# MainBoardR5.net
KiCad netlist of a schematic drawn in EAGLE
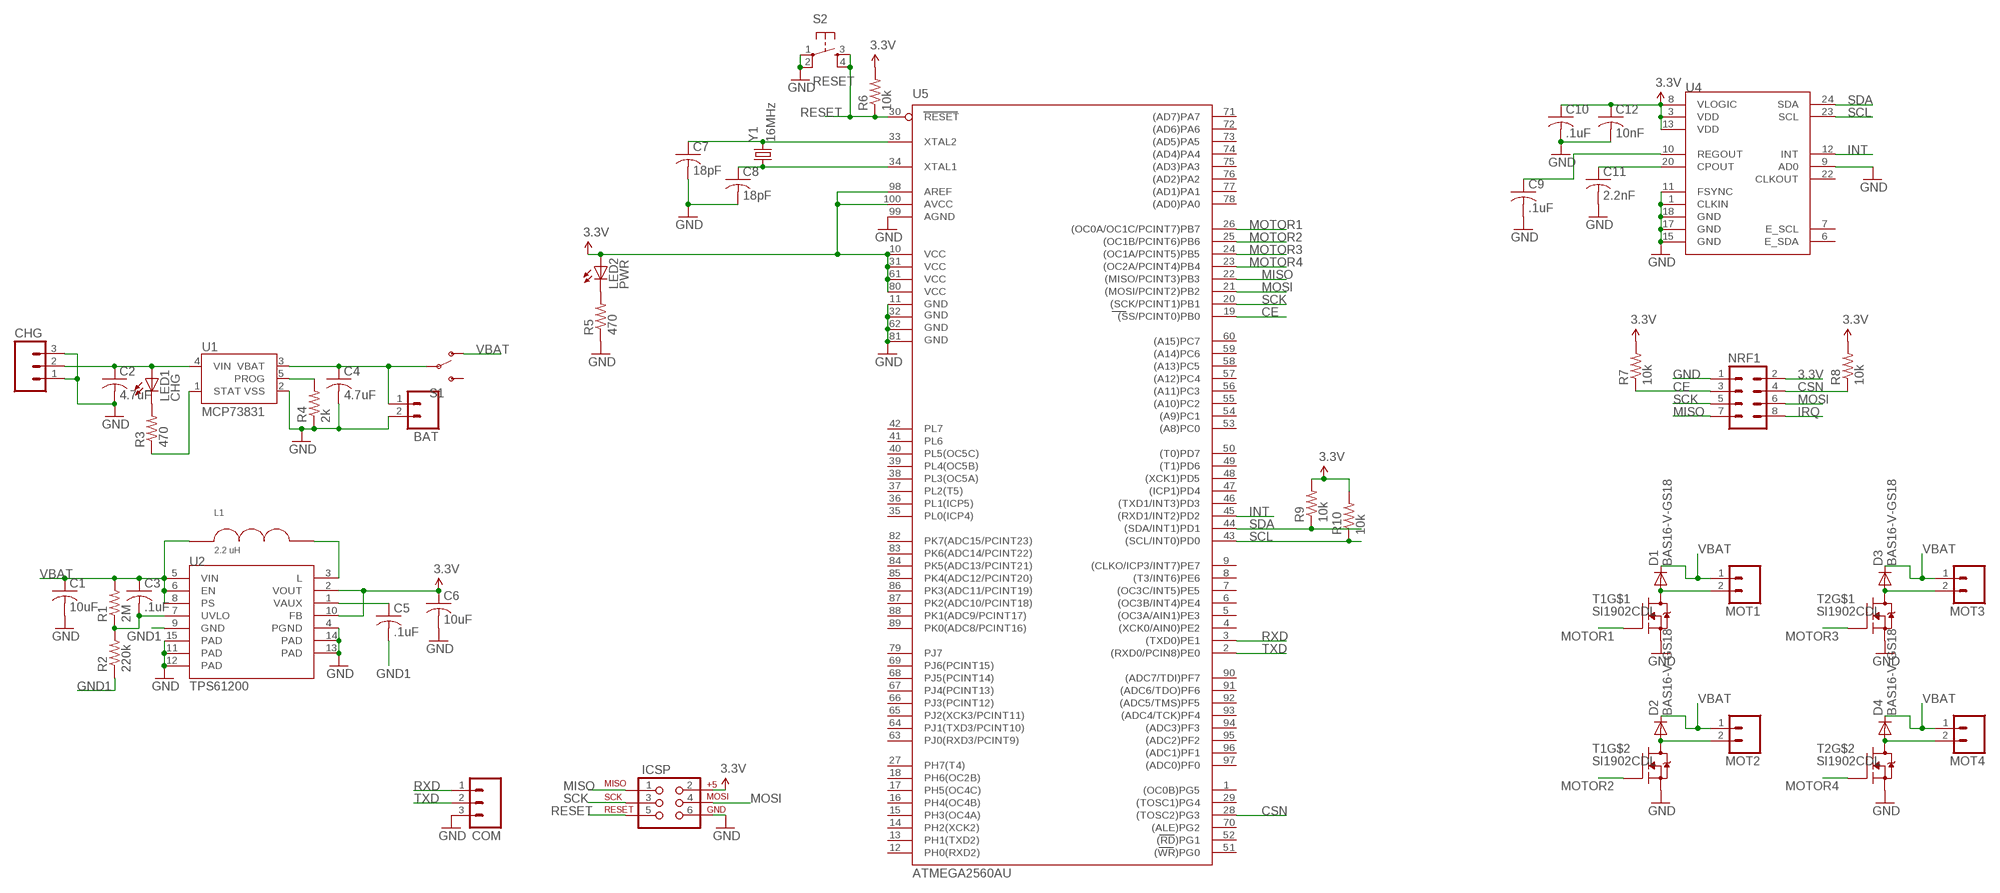
[diagram p0: schematic, sheet 1]

(export (version "E")
  (design (tool "Eeschema 10.0.6"))
  (components
    (comp (ref "BAT")
      (value "M02LOCK_LONGPADS")
      (footprint "eagle-import:1X02_LOCK_LONGPADS")
      (libsource (lib "eagle-import") (part "M02LOCK_LONGPADS"))
    )
    (comp (ref "C1")
      (value "10uF")
      (footprint "eagle-import:C0805")
      (libsource (lib "eagle-import") (part "C-USC0805"))
    )
    (comp (ref "C2")
      (value "4.7uF")
      (footprint "eagle-import:C0805")
      (libsource (lib "eagle-import") (part "C-USC0805"))
    )
    (comp (ref "C3")
      (value ".1uF")
      (footprint "eagle-import:C0805")
      (libsource (lib "eagle-import") (part "C-USC0805"))
    )
    (comp (ref "C4")
      (value "4.7uF")
      (footprint "eagle-import:C0805")
      (libsource (lib "eagle-import") (part "C-USC0805"))
    )
    (comp (ref "C5")
      (value ".1uF")
      (footprint "eagle-import:C0805")
      (libsource (lib "eagle-import") (part "C-USC0805"))
    )
    (comp (ref "C6")
      (value "10uF")
      (footprint "eagle-import:C0805")
      (libsource (lib "eagle-import") (part "C-USC0805"))
    )
    (comp (ref "C7")
      (value "18pF")
      (footprint "eagle-import:C0805")
      (libsource (lib "eagle-import") (part "C-USC0805"))
    )
    (comp (ref "C8")
      (value "18pF")
      (footprint "eagle-import:C0805")
      (libsource (lib "eagle-import") (part "C-USC0805"))
    )
    (comp (ref "C9")
      (value ".1uF")
      (footprint "eagle-import:C0805")
      (libsource (lib "eagle-import") (part "C-USC0805"))
    )
    (comp (ref "C10")
      (value ".1uF")
      (footprint "eagle-import:C0805")
      (libsource (lib "eagle-import") (part "C-USC0805"))
    )
    (comp (ref "C11")
      (value "2.2nF")
      (footprint "eagle-import:C0805")
      (libsource (lib "eagle-import") (part "C-USC0805"))
    )
    (comp (ref "C12")
      (value "10nF")
      (footprint "eagle-import:C0805")
      (libsource (lib "eagle-import") (part "C-USC0805"))
    )
    (comp (ref "CHG")
      (value "M03LONGPADS")
      (footprint "eagle-import:1X03_LONGPADS")
      (libsource (lib "eagle-import") (part "M03LONGPADS"))
    )
    (comp (ref "COM")
      (value "M03LONGPADS")
      (footprint "eagle-import:1X03_LONGPADS")
      (libsource (lib "eagle-import") (part "M03LONGPADS"))
    )
    (comp (ref "D1")
      (value "BAS16-V-GS18")
      (footprint "eagle-import:SOT23")
      (libsource (lib "eagle-import") (part "BAS16-V-GS18"))
    )
    (comp (ref "D2")
      (value "BAS16-V-GS18")
      (footprint "eagle-import:SOT23")
      (libsource (lib "eagle-import") (part "BAS16-V-GS18"))
    )
    (comp (ref "D3")
      (value "BAS16-V-GS18")
      (footprint "eagle-import:SOT23")
      (libsource (lib "eagle-import") (part "BAS16-V-GS18"))
    )
    (comp (ref "D4")
      (value "BAS16-V-GS18")
      (footprint "eagle-import:SOT23")
      (libsource (lib "eagle-import") (part "BAS16-V-GS18"))
    )
    (comp (ref "ICSP")
      (value "AVR_SPI_PRG_62X3_LOCK")
      (footprint "eagle-import:2X3_LOCK")
      (libsource (lib "eagle-import") (part "AVR_SPI_PRG_62X3_LOCK"))
    )
    (comp (ref "L1")
      (value "2.2 uH")
      (footprint "eagle-import:2518")
      (libsource (lib "eagle-import") (part "BRHL2518T2R2M"))
    )
    (comp (ref "LED1")
      (value "CHG")
      (footprint "eagle-import:LED-1206")
      (libsource (lib "eagle-import") (part "LED1206"))
    )
    (comp (ref "LED2")
      (value "PWR")
      (footprint "eagle-import:LED-1206")
      (libsource (lib "eagle-import") (part "LED1206"))
    )
    (comp (ref "MOT1")
      (value "M02LOCK_LONGPADS")
      (footprint "eagle-import:1X02_LOCK_LONGPADS")
      (libsource (lib "eagle-import") (part "M02LOCK_LONGPADS"))
    )
    (comp (ref "MOT2")
      (value "M02LOCK_LONGPADS")
      (footprint "eagle-import:1X02_LOCK_LONGPADS")
      (libsource (lib "eagle-import") (part "M02LOCK_LONGPADS"))
    )
    (comp (ref "MOT3")
      (value "M02LOCK_LONGPADS")
      (footprint "eagle-import:1X02_LOCK_LONGPADS")
      (libsource (lib "eagle-import") (part "M02LOCK_LONGPADS"))
    )
    (comp (ref "MOT4")
      (value "M02LOCK_LONGPADS")
      (footprint "eagle-import:1X02_LOCK_LONGPADS")
      (libsource (lib "eagle-import") (part "M02LOCK_LONGPADS"))
    )
    (comp (ref "NRF1")
      (value "M04X2")
      (footprint "eagle-import:2X4")
      (libsource (lib "eagle-import") (part "M04X2"))
    )
    (comp (ref "R1")
      (value "2M")
      (footprint "eagle-import:0805")
      (libsource (lib "eagle-import") (part "RESISTOR0805-RES"))
    )
    (comp (ref "R2")
      (value "220k")
      (footprint "eagle-import:0805")
      (libsource (lib "eagle-import") (part "RESISTOR0805-RES"))
    )
    (comp (ref "R3")
      (value "470")
      (footprint "eagle-import:0805")
      (libsource (lib "eagle-import") (part "RESISTOR0805-RES"))
    )
    (comp (ref "R4")
      (value "2k")
      (footprint "eagle-import:0805")
      (libsource (lib "eagle-import") (part "RESISTOR0805-RES"))
    )
    (comp (ref "R5")
      (value "470")
      (footprint "eagle-import:0805")
      (libsource (lib "eagle-import") (part "RESISTOR0805-RES"))
    )
    (comp (ref "R6")
      (value "10k")
      (footprint "eagle-import:0805")
      (libsource (lib "eagle-import") (part "RESISTOR0805-RES"))
    )
    (comp (ref "R7")
      (value "10k")
      (footprint "eagle-import:0805")
      (libsource (lib "eagle-import") (part "RESISTOR0805-RES"))
    )
    (comp (ref "R8")
      (value "10k")
      (footprint "eagle-import:0805")
      (libsource (lib "eagle-import") (part "RESISTOR0805-RES"))
    )
    (comp (ref "R9")
      (value "10k")
      (footprint "eagle-import:0805")
      (libsource (lib "eagle-import") (part "RESISTOR0805-RES"))
    )
    (comp (ref "R10")
      (value "10k")
      (footprint "eagle-import:0805")
      (libsource (lib "eagle-import") (part "RESISTOR0805-RES"))
    )
    (comp (ref "S1")
      (value "SWITCH-SPST-SMD-A")
      (footprint "eagle-import:SWITCH-SPST-SMD-A")
      (libsource (lib "eagle-import") (part "SWITCH-SPST-SMD-A"))
    )
    (comp (ref "S2")
      (value "RESET")
      (footprint "eagle-import:TACTILE_SWITCH_SMD")
      (libsource (lib "eagle-import") (part "TAC_SWITCHSMD"))
    )
    (comp (ref "T1")
      (value "SI1902CDL")
      (footprint "eagle-import:SOT363_INFINEON")
      (libsource (lib "eagle-import") (part "SI1902CDL"))
    )
    (comp (ref "T2")
      (value "SI1902CDL")
      (footprint "eagle-import:SOT363_INFINEON")
      (libsource (lib "eagle-import") (part "SI1902CDL"))
    )
    (comp (ref "U1")
      (value "MCP73831")
      (footprint "eagle-import:SOT23-5")
      (libsource (lib "eagle-import") (part "MCP73831"))
    )
    (comp (ref "U2")
      (value "TPS61200")
      (footprint "eagle-import:QFN-10_PAD")
      (libsource (lib "eagle-import") (part "TPS61200"))
    )
    (comp (ref "U4")
      (value "MPU-9150QFN-24-NP")
      (footprint "eagle-import:QFN-24-NP")
      (libsource (lib "eagle-import") (part "MPU-9150QFN-24-NP"))
    )
    (comp (ref "U5")
      (value "ATMEGA2560AU")
      (footprint "eagle-import:TQFP100")
      (libsource (lib "eagle-import") (part "ATMEGA2560AU"))
    )
    (comp (ref "Y1")
      (value "16MHz")
      (footprint "eagle-import:CRYSTAL-SMD-5X3")
      (libsource (lib "eagle-import") (part "CRYSTAL5X3"))
    )
  )
  (nets
    (net (code "1") (name "/CE") (class "Default")
      (node (ref "NRF1") (pin "3") (pinfunction "3_3") (pintype "passive"))
      (node (ref "R7") (pin "1") (pinfunction "1_1") (pintype "passive"))
      (node (ref "U5") (pin "19") (pinfunction "(SS/PCINT0)PB0_19") (pintype "bidirectional"))
    )
    (net (code "2") (name "/CSN") (class "Default")
      (node (ref "NRF1") (pin "4") (pinfunction "4_4") (pintype "passive"))
      (node (ref "R8") (pin "1") (pinfunction "1_1") (pintype "passive"))
      (node (ref "U5") (pin "28") (pinfunction "(TOSC2)PG3_28") (pintype "bidirectional"))
    )
    (net (code "3") (name "/GND1") (class "Default")
      (node (ref "C5") (pin "2") (pinfunction "2_2") (pintype "passive"))
      (node (ref "R2") (pin "1") (pinfunction "1_1") (pintype "passive"))
      (node (ref "U2") (pin "9") (pinfunction "GND_9") (pintype "power_in"))
    )
    (net (code "4") (name "/INT") (class "Default")
      (node (ref "U4") (pin "12") (pinfunction "INT_12") (pintype "bidirectional"))
      (node (ref "U5") (pin "45") (pinfunction "(RXD1/INT2)PD2_45") (pintype "bidirectional"))
    )
    (net (code "5") (name "/IRQ") (class "Default")
      (node (ref "NRF1") (pin "8") (pinfunction "8_8") (pintype "passive"))
    )
    (net (code "6") (name "/MISO") (class "Default")
      (node (ref "ICSP") (pin "1") (pinfunction "1_1") (pintype "passive"))
      (node (ref "NRF1") (pin "7") (pinfunction "7_7") (pintype "passive"))
      (node (ref "U5") (pin "22") (pinfunction "(MISO/PCINT3)PB3_22") (pintype "bidirectional"))
    )
    (net (code "7") (name "/MOSI") (class "Default")
      (node (ref "ICSP") (pin "4") (pinfunction "4_4") (pintype "passive"))
      (node (ref "NRF1") (pin "6") (pinfunction "6_6") (pintype "passive"))
      (node (ref "U5") (pin "21") (pinfunction "(MOSI/PCINT2)PB2_21") (pintype "bidirectional"))
    )
    (net (code "8") (name "/MOTOR1") (class "Default")
      (node (ref "T1") (pin "2") (pinfunction "G_2") (pintype "passive"))
      (node (ref "U5") (pin "26") (pinfunction "(OC0A/OC1C/PCINT7)PB7_26") (pintype "bidirectional"))
    )
    (net (code "9") (name "/MOTOR2") (class "Default")
      (node (ref "T1") (pin "5") (pinfunction "G_5") (pintype "passive"))
      (node (ref "U5") (pin "25") (pinfunction "(OC1B/PCINT6)PB6_25") (pintype "bidirectional"))
    )
    (net (code "10") (name "/MOTOR3") (class "Default")
      (node (ref "T2") (pin "2") (pinfunction "G_2") (pintype "passive"))
      (node (ref "U5") (pin "24") (pinfunction "(OC1A/PCINT5)PB5_24") (pintype "bidirectional"))
    )
    (net (code "11") (name "/MOTOR4") (class "Default")
      (node (ref "T2") (pin "5") (pinfunction "G_5") (pintype "passive"))
      (node (ref "U5") (pin "23") (pinfunction "(OC2A/PCINT4)PB4_23") (pintype "bidirectional"))
    )
    (net (code "12") (name "/RESET") (class "Default")
      (node (ref "ICSP") (pin "5") (pinfunction "5_5") (pintype "passive"))
      (node (ref "R6") (pin "1") (pinfunction "1_1") (pintype "passive"))
      (node (ref "S2") (pin "3") (pinfunction "3_3") (pintype "passive"))
      (node (ref "S2") (pin "4") (pinfunction "4_4") (pintype "passive"))
      (node (ref "U5") (pin "30") (pinfunction "RESET_30") (pintype "input"))
    )
    (net (code "13") (name "/RXD") (class "Default")
      (node (ref "COM") (pin "1") (pinfunction "1_1") (pintype "passive"))
      (node (ref "U5") (pin "3") (pinfunction "(TXD0)PE1_3") (pintype "bidirectional"))
    )
    (net (code "14") (name "/SCK") (class "Default")
      (node (ref "ICSP") (pin "3") (pinfunction "3_3") (pintype "passive"))
      (node (ref "NRF1") (pin "5") (pinfunction "5_5") (pintype "passive"))
      (node (ref "U5") (pin "20") (pinfunction "(SCK/PCINT1)PB1_20") (pintype "bidirectional"))
    )
    (net (code "15") (name "/SCL") (class "Default")
      (node (ref "R10") (pin "1") (pinfunction "1_1") (pintype "passive"))
      (node (ref "U4") (pin "23") (pinfunction "SCL_23") (pintype "bidirectional"))
      (node (ref "U5") (pin "43") (pinfunction "(SCL/INT0)PD0_43") (pintype "bidirectional"))
    )
    (net (code "16") (name "/SDA") (class "Default")
      (node (ref "R9") (pin "1") (pinfunction "1_1") (pintype "passive"))
      (node (ref "U4") (pin "24") (pinfunction "SDA_24") (pintype "bidirectional"))
      (node (ref "U5") (pin "44") (pinfunction "(SDA/INT1)PD1_44") (pintype "bidirectional"))
    )
    (net (code "17") (name "/TXD") (class "Default")
      (node (ref "COM") (pin "2") (pinfunction "2_2") (pintype "passive"))
      (node (ref "U5") (pin "2") (pinfunction "(RXD0/PCIN8)PE0_2") (pintype "bidirectional"))
    )
    (net (code "18") (name "/VBAT") (class "Default")
      (node (ref "C1") (pin "1") (pinfunction "1_1") (pintype "passive"))
      (node (ref "C3") (pin "1") (pinfunction "1_1") (pintype "passive"))
      (node (ref "D1") (pin "3") (pinfunction "C_3") (pintype "passive"))
      (node (ref "D2") (pin "3") (pinfunction "C_3") (pintype "passive"))
      (node (ref "D3") (pin "3") (pinfunction "C_3") (pintype "passive"))
      (node (ref "D4") (pin "3") (pinfunction "C_3") (pintype "passive"))
      (node (ref "L1") (pin "P$1") (pinfunction "1_P$1") (pintype "bidirectional"))
      (node (ref "MOT1") (pin "1") (pinfunction "1_1") (pintype "passive"))
      (node (ref "MOT2") (pin "1") (pinfunction "1_1") (pintype "passive"))
      (node (ref "MOT3") (pin "1") (pinfunction "1_1") (pintype "passive"))
      (node (ref "MOT4") (pin "1") (pinfunction "1_1") (pintype "passive"))
      (node (ref "R1") (pin "2") (pinfunction "2_2") (pintype "passive"))
      (node (ref "S1") (pin "1") (pinfunction "O_1") (pintype "passive"))
      (node (ref "U2") (pin "5") (pinfunction "VIN_5") (pintype "power_in"))
      (node (ref "U2") (pin "6") (pinfunction "EN_6") (pintype "input"))
      (node (ref "U2") (pin "8") (pinfunction "PS_8") (pintype "input"))
    )
    (net (code "19") (name "3.3V") (class "Default")
      (node (ref "C10") (pin "1") (pinfunction "1_1") (pintype "passive"))
      (node (ref "C12") (pin "1") (pinfunction "1_1") (pintype "passive"))
      (node (ref "C6") (pin "1") (pinfunction "1_1") (pintype "passive"))
      (node (ref "ICSP") (pin "2") (pinfunction "2_2") (pintype "passive"))
      (node (ref "LED2") (pin "A") (pinfunction "A_A") (pintype "passive"))
      (node (ref "NRF1") (pin "2") (pinfunction "2_2") (pintype "passive"))
      (node (ref "R10") (pin "2") (pinfunction "2_2") (pintype "passive"))
      (node (ref "R6") (pin "2") (pinfunction "2_2") (pintype "passive"))
      (node (ref "R7") (pin "2") (pinfunction "2_2") (pintype "passive"))
      (node (ref "R8") (pin "2") (pinfunction "2_2") (pintype "passive"))
      (node (ref "R9") (pin "2") (pinfunction "2_2") (pintype "passive"))
      (node (ref "U2") (pin "10") (pinfunction "FB_10") (pintype "passive"))
      (node (ref "U2") (pin "2") (pinfunction "VOUT_2") (pintype "passive"))
      (node (ref "U4") (pin "13") (pinfunction "VDD_13") (pintype "bidirectional"))
      (node (ref "U4") (pin "3") (pinfunction "VDD_3") (pintype "bidirectional"))
      (node (ref "U4") (pin "8") (pinfunction "VLOGIC_8") (pintype "bidirectional"))
      (node (ref "U5") (pin "10") (pinfunction "VCC_10") (pintype "power_in"))
      (node (ref "U5") (pin "100") (pinfunction "AVCC_100") (pintype "power_in"))
      (node (ref "U5") (pin "31") (pinfunction "VCC1_31") (pintype "power_in"))
      (node (ref "U5") (pin "61") (pinfunction "VCC2_61") (pintype "power_in"))
      (node (ref "U5") (pin "80") (pinfunction "VCC3_80") (pintype "power_in"))
      (node (ref "U5") (pin "98") (pinfunction "AREF_98") (pintype "bidirectional"))
    )
    (net (code "20") (name "GND") (class "Default")
      (node (ref "BAT") (pin "2") (pinfunction "2_2") (pintype "passive"))
      (node (ref "C1") (pin "2") (pinfunction "2_2") (pintype "passive"))
      (node (ref "C10") (pin "2") (pinfunction "2_2") (pintype "passive"))
      (node (ref "C11") (pin "2") (pinfunction "2_2") (pintype "passive"))
      (node (ref "C12") (pin "2") (pinfunction "2_2") (pintype "passive"))
      (node (ref "C2") (pin "2") (pinfunction "2_2") (pintype "passive"))
      (node (ref "C4") (pin "2") (pinfunction "2_2") (pintype "passive"))
      (node (ref "C6") (pin "2") (pinfunction "2_2") (pintype "passive"))
      (node (ref "C7") (pin "2") (pinfunction "2_2") (pintype "passive"))
      (node (ref "C8") (pin "2") (pinfunction "2_2") (pintype "passive"))
      (node (ref "C9") (pin "2") (pinfunction "2_2") (pintype "passive"))
      (node (ref "CHG") (pin "1") (pinfunction "1_1") (pintype "passive"))
      (node (ref "CHG") (pin "3") (pinfunction "3_3") (pintype "passive"))
      (node (ref "COM") (pin "3") (pinfunction "3_3") (pintype "passive"))
      (node (ref "ICSP") (pin "6") (pinfunction "6_6") (pintype "passive"))
      (node (ref "NRF1") (pin "1") (pinfunction "1_1") (pintype "passive"))
      (node (ref "R4") (pin "1") (pinfunction "1_1") (pintype "passive"))
      (node (ref "R5") (pin "1") (pinfunction "1_1") (pintype "passive"))
      (node (ref "S2") (pin "1") (pinfunction "1_1") (pintype "passive"))
      (node (ref "S2") (pin "2") (pinfunction "2_2") (pintype "passive"))
      (node (ref "T1") (pin "1") (pinfunction "S_1") (pintype "passive"))
      (node (ref "T1") (pin "4") (pinfunction "S_4") (pintype "passive"))
      (node (ref "T2") (pin "1") (pinfunction "S_1") (pintype "passive"))
      (node (ref "T2") (pin "4") (pinfunction "S_4") (pintype "passive"))
      (node (ref "U1") (pin "2") (pinfunction "VSS_2") (pintype "power_in"))
      (node (ref "U2") (pin "11") (pinfunction "PAD_11") (pintype "power_in"))
      (node (ref "U2") (pin "12") (pinfunction "PAD_12") (pintype "power_in"))
      (node (ref "U2") (pin "13") (pinfunction "PAD_13") (pintype "power_in"))
      (node (ref "U2") (pin "14") (pinfunction "PAD_14") (pintype "power_in"))
      (node (ref "U2") (pin "15") (pinfunction "PAD_15") (pintype "power_in"))
      (node (ref "U2") (pin "4") (pinfunction "PGND_4") (pintype "power_in"))
      (node (ref "U4") (pin "1") (pinfunction "CLKIN_1") (pintype "bidirectional"))
      (node (ref "U4") (pin "11") (pinfunction "FSYNC_11") (pintype "bidirectional"))
      (node (ref "U4") (pin "15") (pinfunction "GND_15") (pintype "bidirectional"))
      (node (ref "U4") (pin "17") (pinfunction "GND_17") (pintype "bidirectional"))
      (node (ref "U4") (pin "18") (pinfunction "GND_18") (pintype "bidirectional"))
      (node (ref "U4") (pin "9") (pinfunction "AD0_9") (pintype "bidirectional"))
      (node (ref "U5") (pin "11") (pinfunction "GND_11") (pintype "power_in"))
      (node (ref "U5") (pin "32") (pinfunction "GND1_32") (pintype "power_in"))
      (node (ref "U5") (pin "62") (pinfunction "GND2_62") (pintype "power_in"))
      (node (ref "U5") (pin "81") (pinfunction "GND3_81") (pintype "power_in"))
      (node (ref "U5") (pin "99") (pinfunction "AGND_99") (pintype "power_in"))
    )
    (net (code "21") (name "Net-(D1-A)") (class "Default")
      (node (ref "D1") (pin "1") (pinfunction "A_1") (pintype "passive"))
      (node (ref "MOT1") (pin "2") (pinfunction "2_2") (pintype "passive"))
      (node (ref "T1") (pin "6") (pinfunction "D_6") (pintype "passive"))
    )
    (net (code "22") (name "Net-(D2-A)") (class "Default")
      (node (ref "D2") (pin "1") (pinfunction "A_1") (pintype "passive"))
      (node (ref "MOT2") (pin "2") (pinfunction "2_2") (pintype "passive"))
      (node (ref "T1") (pin "3") (pinfunction "D_3") (pintype "passive"))
    )
    (net (code "23") (name "Net-(D3-A)") (class "Default")
      (node (ref "D3") (pin "1") (pinfunction "A_1") (pintype "passive"))
      (node (ref "MOT3") (pin "2") (pinfunction "2_2") (pintype "passive"))
      (node (ref "T2") (pin "6") (pinfunction "D_6") (pintype "passive"))
    )
    (net (code "24") (name "Net-(D4-A)") (class "Default")
      (node (ref "D4") (pin "1") (pinfunction "A_1") (pintype "passive"))
      (node (ref "MOT4") (pin "2") (pinfunction "2_2") (pintype "passive"))
      (node (ref "T2") (pin "3") (pinfunction "D_3") (pintype "passive"))
    )
    (net (code "25") (name "Net-(L1-2)") (class "Default")
      (node (ref "L1") (pin "P$2") (pinfunction "2_P$2") (pintype "bidirectional"))
      (node (ref "U2") (pin "3") (pinfunction "L_3") (pintype "passive"))
    )
    (net (code "26") (name "Net-(LED1-PadC)") (class "Default")
      (node (ref "LED1") (pin "C") (pinfunction "C_C") (pintype "passive"))
      (node (ref "R3") (pin "2") (pinfunction "2_2") (pintype "passive"))
    )
    (net (code "27") (name "Net-(LED2-PadC)") (class "Default")
      (node (ref "LED2") (pin "C") (pinfunction "C_C") (pintype "passive"))
      (node (ref "R5") (pin "2") (pinfunction "2_2") (pintype "passive"))
    )
    (net (code "28") (name "Net-(S1-P)") (class "Default")
      (node (ref "BAT") (pin "1") (pinfunction "1_1") (pintype "passive"))
      (node (ref "C4") (pin "1") (pinfunction "1_1") (pintype "passive"))
      (node (ref "S1") (pin "2") (pinfunction "P_2") (pintype "passive"))
      (node (ref "U1") (pin "3") (pinfunction "VBAT_3") (pintype "power_in"))
    )
    (net (code "29") (name "Net-(U1-PROG)") (class "Default")
      (node (ref "R4") (pin "2") (pinfunction "2_2") (pintype "passive"))
      (node (ref "U1") (pin "5") (pinfunction "PROG_5") (pintype "input"))
    )
    (net (code "30") (name "Net-(U1-STAT)") (class "Default")
      (node (ref "R3") (pin "1") (pinfunction "1_1") (pintype "passive"))
      (node (ref "U1") (pin "1") (pinfunction "STAT_1") (pintype "output"))
    )
    (net (code "31") (name "Net-(U1-VIN)") (class "Default")
      (node (ref "C2") (pin "1") (pinfunction "1_1") (pintype "passive"))
      (node (ref "CHG") (pin "2") (pinfunction "2_2") (pintype "passive"))
      (node (ref "LED1") (pin "A") (pinfunction "A_A") (pintype "passive"))
      (node (ref "U1") (pin "4") (pinfunction "VIN_4") (pintype "power_in"))
    )
    (net (code "32") (name "Net-(U2-UVLO)") (class "Default")
      (node (ref "C3") (pin "2") (pinfunction "2_2") (pintype "passive"))
      (node (ref "R1") (pin "1") (pinfunction "1_1") (pintype "passive"))
      (node (ref "R2") (pin "2") (pinfunction "2_2") (pintype "passive"))
      (node (ref "U2") (pin "7") (pinfunction "UVLO_7") (pintype "passive"))
    )
    (net (code "33") (name "Net-(U2-VAUX)") (class "Default")
      (node (ref "C5") (pin "1") (pinfunction "1_1") (pintype "passive"))
      (node (ref "U2") (pin "1") (pinfunction "VAUX_1") (pintype "passive"))
    )
    (net (code "34") (name "Net-(U4-CPOUT)") (class "Default")
      (node (ref "C11") (pin "1") (pinfunction "1_1") (pintype "passive"))
      (node (ref "U4") (pin "20") (pinfunction "CPOUT_20") (pintype "bidirectional"))
    )
    (net (code "35") (name "Net-(U4-REGOUT)") (class "Default")
      (node (ref "C9") (pin "1") (pinfunction "1_1") (pintype "passive"))
      (node (ref "U4") (pin "10") (pinfunction "REGOUT_10") (pintype "bidirectional"))
    )
    (net (code "36") (name "Net-(U5-XTAL1)") (class "Default")
      (node (ref "C8") (pin "1") (pinfunction "1_1") (pintype "passive"))
      (node (ref "U5") (pin "34") (pinfunction "XTAL1_34") (pintype "input"))
      (node (ref "Y1") (pin "1") (pinfunction "1_1") (pintype "passive"))
    )
    (net (code "37") (name "Net-(U5-XTAL2)") (class "Default")
      (node (ref "C7") (pin "1") (pinfunction "1_1") (pintype "passive"))
      (node (ref "U5") (pin "33") (pinfunction "XTAL2_33") (pintype "output"))
      (node (ref "Y1") (pin "3") (pinfunction "2_3") (pintype "passive"))
    )
    (net (code "38") (name "unconnected-(S1-S-Pad3)") (class "Default")
      (node (ref "S1") (pin "3") (pinfunction "S_3") (pintype "passive"))
    )
    (net (code "39") (name "unconnected-(U4-CLKOUT-Pad22)") (class "Default")
      (node (ref "U4") (pin "22") (pinfunction "CLKOUT_22") (pintype "bidirectional"))
    )
    (net (code "40") (name "unconnected-(U4-E_SCL-Pad7)") (class "Default")
      (node (ref "U4") (pin "7") (pinfunction "E_SCL_7") (pintype "bidirectional"))
    )
    (net (code "41") (name "unconnected-(U4-E_SDA-Pad6)") (class "Default")
      (node (ref "U4") (pin "6") (pinfunction "E_SDA_6") (pintype "bidirectional"))
    )
    (net (code "42") (name "unconnected-(U5-(A8)PC0-Pad53)") (class "Default")
      (node (ref "U5") (pin "53") (pinfunction "(A8)PC0_53") (pintype "bidirectional"))
    )
    (net (code "43") (name "unconnected-(U5-(A9)PC1-Pad54)") (class "Default")
      (node (ref "U5") (pin "54") (pinfunction "(A9)PC1_54") (pintype "bidirectional"))
    )
    (net (code "44") (name "unconnected-(U5-(A10)PC2-Pad55)") (class "Default")
      (node (ref "U5") (pin "55") (pinfunction "(A10)PC2_55") (pintype "bidirectional"))
    )
    (net (code "45") (name "unconnected-(U5-(A11)PC3-Pad56)") (class "Default")
      (node (ref "U5") (pin "56") (pinfunction "(A11)PC3_56") (pintype "bidirectional"))
    )
    (net (code "46") (name "unconnected-(U5-(A12)PC4-Pad57)") (class "Default")
      (node (ref "U5") (pin "57") (pinfunction "(A12)PC4_57") (pintype "bidirectional"))
    )
    (net (code "47") (name "unconnected-(U5-(A13)PC5-Pad58)") (class "Default")
      (node (ref "U5") (pin "58") (pinfunction "(A13)PC5_58") (pintype "bidirectional"))
    )
    (net (code "48") (name "unconnected-(U5-(A14)PC6-Pad59)") (class "Default")
      (node (ref "U5") (pin "59") (pinfunction "(A14)PC6_59") (pintype "bidirectional"))
    )
    (net (code "49") (name "unconnected-(U5-(A15)PC7-Pad60)") (class "Default")
      (node (ref "U5") (pin "60") (pinfunction "(A15)PC7_60") (pintype "bidirectional"))
    )
    (net (code "50") (name "unconnected-(U5-(AD0)PA0-Pad78)") (class "Default")
      (node (ref "U5") (pin "78") (pinfunction "(AD0)PA0_78") (pintype "bidirectional"))
    )
    (net (code "51") (name "unconnected-(U5-(AD1)PA1-Pad77)") (class "Default")
      (node (ref "U5") (pin "77") (pinfunction "(AD1)PA1_77") (pintype "bidirectional"))
    )
    (net (code "52") (name "unconnected-(U5-(AD2)PA2-Pad76)") (class "Default")
      (node (ref "U5") (pin "76") (pinfunction "(AD2)PA2_76") (pintype "bidirectional"))
    )
    (net (code "53") (name "unconnected-(U5-(AD3)PA3-Pad75)") (class "Default")
      (node (ref "U5") (pin "75") (pinfunction "(AD3)PA3_75") (pintype "bidirectional"))
    )
    (net (code "54") (name "unconnected-(U5-(AD4)PA4-Pad74)") (class "Default")
      (node (ref "U5") (pin "74") (pinfunction "(AD4)PA4_74") (pintype "bidirectional"))
    )
    (net (code "55") (name "unconnected-(U5-(AD5)PA5-Pad73)") (class "Default")
      (node (ref "U5") (pin "73") (pinfunction "(AD5)PA5_73") (pintype "bidirectional"))
    )
    (net (code "56") (name "unconnected-(U5-(AD6)PA6-Pad72)") (class "Default")
      (node (ref "U5") (pin "72") (pinfunction "(AD6)PA6_72") (pintype "bidirectional"))
    )
    (net (code "57") (name "unconnected-(U5-(AD7)PA7-Pad71)") (class "Default")
      (node (ref "U5") (pin "71") (pinfunction "(AD7)PA7_71") (pintype "bidirectional"))
    )
    (net (code "58") (name "unconnected-(U5-(ADC0)PF0-Pad97)") (class "Default")
      (node (ref "U5") (pin "97") (pinfunction "(ADC0)PF0_97") (pintype "bidirectional"))
    )
    (net (code "59") (name "unconnected-(U5-(ADC1)PF1-Pad96)") (class "Default")
      (node (ref "U5") (pin "96") (pinfunction "(ADC1)PF1_96") (pintype "bidirectional"))
    )
    (net (code "60") (name "unconnected-(U5-(ADC2)PF2-Pad95)") (class "Default")
      (node (ref "U5") (pin "95") (pinfunction "(ADC2)PF2_95") (pintype "bidirectional"))
    )
    (net (code "61") (name "unconnected-(U5-(ADC3)PF3-Pad94)") (class "Default")
      (node (ref "U5") (pin "94") (pinfunction "(ADC3)PF3_94") (pintype "bidirectional"))
    )
    (net (code "62") (name "unconnected-(U5-(ADC4{slash}TCK)PF4-Pad93)") (class "Default")
      (node (ref "U5") (pin "93") (pinfunction "(ADC4/TCK)PF4_93") (pintype "bidirectional"))
    )
    (net (code "63") (name "unconnected-(U5-(ADC5{slash}TMS)PF5-Pad92)") (class "Default")
      (node (ref "U5") (pin "92") (pinfunction "(ADC5/TMS)PF5_92") (pintype "bidirectional"))
    )
    (net (code "64") (name "unconnected-(U5-(ADC6{slash}TDO)PF6-Pad91)") (class "Default")
      (node (ref "U5") (pin "91") (pinfunction "(ADC6/TDO)PF6_91") (pintype "bidirectional"))
    )
    (net (code "65") (name "unconnected-(U5-(ADC7{slash}TDI)PF7-Pad90)") (class "Default")
      (node (ref "U5") (pin "90") (pinfunction "(ADC7/TDI)PF7_90") (pintype "bidirectional"))
    )
    (net (code "66") (name "unconnected-(U5-(ALE)PG2-Pad70)") (class "Default")
      (node (ref "U5") (pin "70") (pinfunction "(ALE)PG2_70") (pintype "bidirectional"))
    )
    (net (code "67") (name "unconnected-(U5-(CLKO{slash}ICP3{slash}INT7)PE7-Pad9)") (class "Default")
      (node (ref "U5") (pin "9") (pinfunction "(CLKO/ICP3/INT7)PE7_9") (pintype "bidirectional"))
    )
    (net (code "68") (name "unconnected-(U5-(ICP1)PD4-Pad47)") (class "Default")
      (node (ref "U5") (pin "47") (pinfunction "(ICP1)PD4_47") (pintype "bidirectional"))
    )
    (net (code "69") (name "unconnected-(U5-(OC0B)PG5-Pad1)") (class "Default")
      (node (ref "U5") (pin "1") (pinfunction "(OC0B)PG5_1") (pintype "bidirectional"))
    )
    (net (code "70") (name "unconnected-(U5-(OC3A{slash}AIN1)PE3-Pad5)") (class "Default")
      (node (ref "U5") (pin "5") (pinfunction "(OC3A/AIN1)PE3_5") (pintype "bidirectional"))
    )
    (net (code "71") (name "unconnected-(U5-(OC3B{slash}INT4)PE4-Pad6)") (class "Default")
      (node (ref "U5") (pin "6") (pinfunction "(OC3B/INT4)PE4_6") (pintype "bidirectional"))
    )
    (net (code "72") (name "unconnected-(U5-(OC3C{slash}INT5)PE5-Pad7)") (class "Default")
      (node (ref "U5") (pin "7") (pinfunction "(OC3C/INT5)PE5_7") (pintype "bidirectional"))
    )
    (net (code "73") (name "unconnected-(U5-(RD)PG1-Pad52)") (class "Default")
      (node (ref "U5") (pin "52") (pinfunction "(RD)PG1_52") (pintype "bidirectional"))
    )
    (net (code "74") (name "unconnected-(U5-(T0)PD7-Pad50)") (class "Default")
      (node (ref "U5") (pin "50") (pinfunction "(T0)PD7_50") (pintype "bidirectional"))
    )
    (net (code "75") (name "unconnected-(U5-(T1)PD6-Pad49)") (class "Default")
      (node (ref "U5") (pin "49") (pinfunction "(T1)PD6_49") (pintype "bidirectional"))
    )
    (net (code "76") (name "unconnected-(U5-(T3{slash}INT6)PE6-Pad8)") (class "Default")
      (node (ref "U5") (pin "8") (pinfunction "(T3/INT6)PE6_8") (pintype "bidirectional"))
    )
    (net (code "77") (name "unconnected-(U5-(TOSC1)PG4-Pad29)") (class "Default")
      (node (ref "U5") (pin "29") (pinfunction "(TOSC1)PG4_29") (pintype "bidirectional"))
    )
    (net (code "78") (name "unconnected-(U5-(TXD1{slash}INT3)PD3-Pad46)") (class "Default")
      (node (ref "U5") (pin "46") (pinfunction "(TXD1/INT3)PD3_46") (pintype "bidirectional"))
    )
    (net (code "79") (name "unconnected-(U5-(WR)PG0-Pad51)") (class "Default")
      (node (ref "U5") (pin "51") (pinfunction "(WR)PG0_51") (pintype "bidirectional"))
    )
    (net (code "80") (name "unconnected-(U5-(XCK0{slash}AIN0)PE2-Pad4)") (class "Default")
      (node (ref "U5") (pin "4") (pinfunction "(XCK0/AIN0)PE2_4") (pintype "bidirectional"))
    )
    (net (code "81") (name "unconnected-(U5-(XCK1)PD5-Pad48)") (class "Default")
      (node (ref "U5") (pin "48") (pinfunction "(XCK1)PD5_48") (pintype "bidirectional"))
    )
    (net (code "82") (name "unconnected-(U5-PH0(RXD2)-Pad12)") (class "Default")
      (node (ref "U5") (pin "12") (pinfunction "PH0(RXD2)_12") (pintype "bidirectional"))
    )
    (net (code "83") (name "unconnected-(U5-PH1(TXD2)-Pad13)") (class "Default")
      (node (ref "U5") (pin "13") (pinfunction "PH1(TXD2)_13") (pintype "bidirectional"))
    )
    (net (code "84") (name "unconnected-(U5-PH2(XCK2)-Pad14)") (class "Default")
      (node (ref "U5") (pin "14") (pinfunction "PH2(XCK2)_14") (pintype "bidirectional"))
    )
    (net (code "85") (name "unconnected-(U5-PH3(OC4A)-Pad15)") (class "Default")
      (node (ref "U5") (pin "15") (pinfunction "PH3(OC4A)_15") (pintype "bidirectional"))
    )
    (net (code "86") (name "unconnected-(U5-PH4(OC4B)-Pad16)") (class "Default")
      (node (ref "U5") (pin "16") (pinfunction "PH4(OC4B)_16") (pintype "bidirectional"))
    )
    (net (code "87") (name "unconnected-(U5-PH5(OC4C)-Pad17)") (class "Default")
      (node (ref "U5") (pin "17") (pinfunction "PH5(OC4C)_17") (pintype "bidirectional"))
    )
    (net (code "88") (name "unconnected-(U5-PH6(OC2B)-Pad18)") (class "Default")
      (node (ref "U5") (pin "18") (pinfunction "PH6(OC2B)_18") (pintype "bidirectional"))
    )
    (net (code "89") (name "unconnected-(U5-PH7(T4)-Pad27)") (class "Default")
      (node (ref "U5") (pin "27") (pinfunction "PH7(T4)_27") (pintype "bidirectional"))
    )
    (net (code "90") (name "unconnected-(U5-PJ0(RXD3{slash}PCINT9)-Pad63)") (class "Default")
      (node (ref "U5") (pin "63") (pinfunction "PJ0(RXD3/PCINT9)_63") (pintype "bidirectional"))
    )
    (net (code "91") (name "unconnected-(U5-PJ1(TXD3{slash}PCINT10)-Pad64)") (class "Default")
      (node (ref "U5") (pin "64") (pinfunction "PJ1(TXD3/PCINT10)_64") (pintype "bidirectional"))
    )
    (net (code "92") (name "unconnected-(U5-PJ2(XCK3{slash}PCINT11)-Pad65)") (class "Default")
      (node (ref "U5") (pin "65") (pinfunction "PJ2(XCK3/PCINT11)_65") (pintype "bidirectional"))
    )
    (net (code "93") (name "unconnected-(U5-PJ3(PCINT12)-Pad66)") (class "Default")
      (node (ref "U5") (pin "66") (pinfunction "PJ3(PCINT12)_66") (pintype "bidirectional"))
    )
    (net (code "94") (name "unconnected-(U5-PJ4(PCINT13)-Pad67)") (class "Default")
      (node (ref "U5") (pin "67") (pinfunction "PJ4(PCINT13)_67") (pintype "bidirectional"))
    )
    (net (code "95") (name "unconnected-(U5-PJ5(PCINT14)-Pad68)") (class "Default")
      (node (ref "U5") (pin "68") (pinfunction "PJ5(PCINT14)_68") (pintype "bidirectional"))
    )
    (net (code "96") (name "unconnected-(U5-PJ6(PCINT15)-Pad69)") (class "Default")
      (node (ref "U5") (pin "69") (pinfunction "PJ6(PCINT15)_69") (pintype "bidirectional"))
    )
    (net (code "97") (name "unconnected-(U5-PJ7-Pad79)") (class "Default")
      (node (ref "U5") (pin "79") (pinfunction "PJ7_79") (pintype "bidirectional"))
    )
    (net (code "98") (name "unconnected-(U5-PK0(ADC8{slash}PCINT16)-Pad89)") (class "Default")
      (node (ref "U5") (pin "89") (pinfunction "PK0(ADC8/PCINT16)_89") (pintype "bidirectional"))
    )
    (net (code "99") (name "unconnected-(U5-PK1(ADC9{slash}PCINT17)-Pad88)") (class "Default")
      (node (ref "U5") (pin "88") (pinfunction "PK1(ADC9/PCINT17)_88") (pintype "bidirectional"))
    )
    (net (code "100") (name "unconnected-(U5-PK2(ADC10{slash}PCINT18)-Pad87)") (class "Default")
      (node (ref "U5") (pin "87") (pinfunction "PK2(ADC10/PCINT18)_87") (pintype "bidirectional"))
    )
    (net (code "101") (name "unconnected-(U5-PK3(ADC11{slash}PCINT19)-Pad86)") (class "Default")
      (node (ref "U5") (pin "86") (pinfunction "PK3(ADC11/PCINT19)_86") (pintype "bidirectional"))
    )
    (net (code "102") (name "unconnected-(U5-PK4(ADC12{slash}PCINT20)-Pad85)") (class "Default")
      (node (ref "U5") (pin "85") (pinfunction "PK4(ADC12/PCINT20)_85") (pintype "bidirectional"))
    )
    (net (code "103") (name "unconnected-(U5-PK5(ADC13{slash}PCINT21)-Pad84)") (class "Default")
      (node (ref "U5") (pin "84") (pinfunction "PK5(ADC13/PCINT21)_84") (pintype "bidirectional"))
    )
    (net (code "104") (name "unconnected-(U5-PK6(ADC14{slash}PCINT22)-Pad83)") (class "Default")
      (node (ref "U5") (pin "83") (pinfunction "PK6(ADC14/PCINT22)_83") (pintype "bidirectional"))
    )
    (net (code "105") (name "unconnected-(U5-PK7(ADC15{slash}PCINT23)-Pad82)") (class "Default")
      (node (ref "U5") (pin "82") (pinfunction "PK7(ADC15/PCINT23)_82") (pintype "bidirectional"))
    )
    (net (code "106") (name "unconnected-(U5-PL0(ICP4)-Pad35)") (class "Default")
      (node (ref "U5") (pin "35") (pinfunction "PL0(ICP4)_35") (pintype "bidirectional"))
    )
    (net (code "107") (name "unconnected-(U5-PL1(ICP5)-Pad36)") (class "Default")
      (node (ref "U5") (pin "36") (pinfunction "PL1(ICP5)_36") (pintype "bidirectional"))
    )
    (net (code "108") (name "unconnected-(U5-PL2(T5)-Pad37)") (class "Default")
      (node (ref "U5") (pin "37") (pinfunction "PL2(T5)_37") (pintype "bidirectional"))
    )
    (net (code "109") (name "unconnected-(U5-PL3(OC5A)-Pad38)") (class "Default")
      (node (ref "U5") (pin "38") (pinfunction "PL3(OC5A)_38") (pintype "bidirectional"))
    )
    (net (code "110") (name "unconnected-(U5-PL4(OC5B)-Pad39)") (class "Default")
      (node (ref "U5") (pin "39") (pinfunction "PL4(OC5B)_39") (pintype "bidirectional"))
    )
    (net (code "111") (name "unconnected-(U5-PL5(OC5C)-Pad40)") (class "Default")
      (node (ref "U5") (pin "40") (pinfunction "PL5(OC5C)_40") (pintype "bidirectional"))
    )
    (net (code "112") (name "unconnected-(U5-PL6-Pad41)") (class "Default")
      (node (ref "U5") (pin "41") (pinfunction "PL6_41") (pintype "bidirectional"))
    )
    (net (code "113") (name "unconnected-(U5-PL7-Pad42)") (class "Default")
      (node (ref "U5") (pin "42") (pinfunction "PL7_42") (pintype "bidirectional"))
    )
  )
)
